# Alim_Ticketing_Slave.net
KiCad netlist of a schematic drawn in Altium Designer
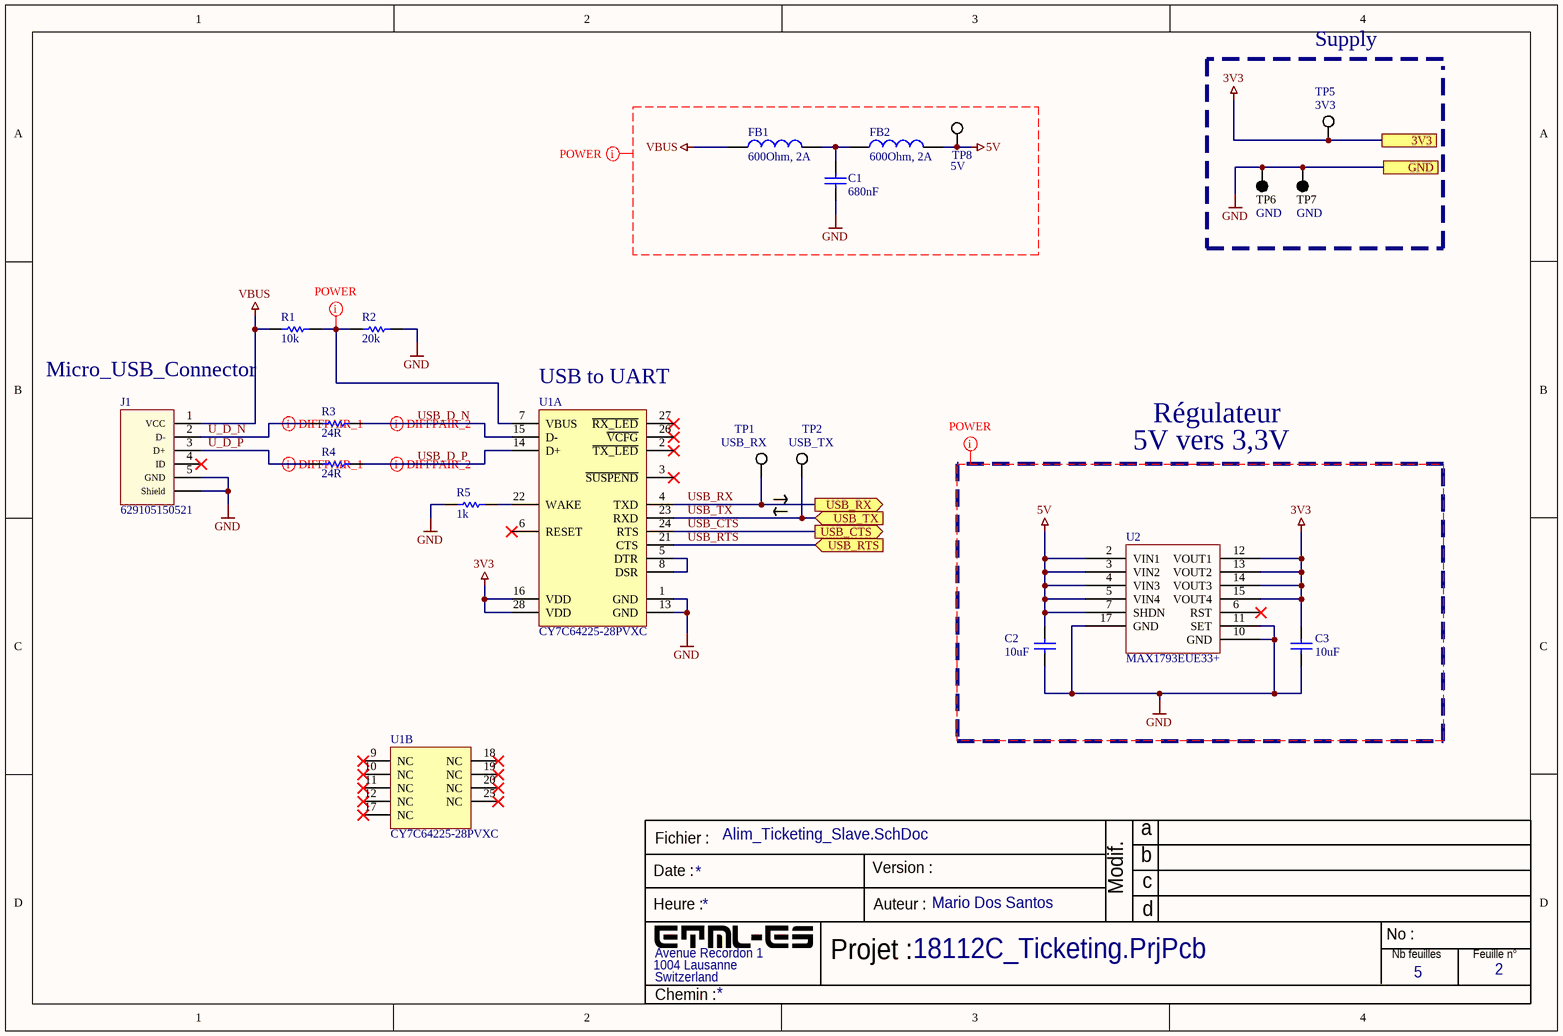
[diagram p0: Alim_Ticketing_Slave.SchDoc]

(export (version "E")
  (design (tool "Eeschema 10.0.6"))
  (components
    (comp (ref "C1")
      (value "680nF")
      (footprint "6-0805_N")
      (description "WCAP-CSGP General Purpose Ceramic Capacitors, size 0805, 100nF, +/-10%, 50VDC")
      (libsource (lib "VPA_v2b") (part "885012207098"))
    )
    (comp (ref "C2")
      (value "10uF")
      (footprint "6-0805_N")
      (description "Capacitor")
      (fields (field (name "PUBLISHER") "Altium Limited"))
      (libsource (lib "Miscellaneous Devices") (part "Cap"))
    )
    (comp (ref "C3")
      (value "10uF")
      (footprint "6-0805_N")
      (description "Capacitor")
      (fields (field (name "PUBLISHER") "Altium Limited"))
      (libsource (lib "Miscellaneous Devices") (part "Cap"))
    )
    (comp (ref "FB1")
      (value "600Ohm, 2A")
      (footprint "WE-CBF_0805_High Current")
      (description "WE-CBF SMT EMI Suppression Ferrite Bead, size 0805, 600Ohm, 2A")
      (fields (field (name "PART NUMBER") "742792040") (field (name "PUBLISHER") "Wurth Elektronik"))
      (libsource (lib "VPA_v2b") (part "742792040"))
    )
    (comp (ref "FB2")
      (value "600Ohm, 2A")
      (footprint "WE-CBF_0805_High Current")
      (description "WE-CBF SMT EMI Suppression Ferrite Bead, size 0805, 600Ohm, 2A")
      (fields (field (name "PART NUMBER") "742792040") (field (name "PUBLISHER") "Wurth Elektronik"))
      (libsource (lib "VPA_v2b") (part "742792040"))
    )
    (comp (ref "J1")
      (value "629105150521")
      (footprint "629105150521")
      (description "Micro USB 2.0 SMT Type B Horizontal 5 Contacts High Current WR-COM")
      (fields (field (name "PART NUMBER") "732-5960-1-ND") (field (name "PUBLISHER") "Wurth Elektronik"))
      (libsource (lib "PCB_Ticketing_Slave") (part "629105150521"))
    )
    (comp (ref "R1")
      (value "10k")
      (footprint "RESC0805(2012)_L")
      (description "100K 0.125W 5% 0805 (2012 Metric)  SMD")
      (fields (field (name "TOLERANCE") "5 %") (field (name "POWER") "0.125 W"))
      (libsource (lib "Altium Content Vault") (part "CMP-1013-00122-1"))
    )
    (comp (ref "R2")
      (value "20k")
      (footprint "RESC0805(2012)_L")
      (description "100K 0.125W 5% 0805 (2012 Metric)  SMD")
      (fields (field (name "TOLERANCE") "5 %") (field (name "POWER") "0.125 W"))
      (libsource (lib "Altium Content Vault") (part "CMP-1013-00122-1"))
    )
    (comp (ref "R3")
      (value "24R")
      (footprint "RESC0805(2012)_L")
      (description "100K 0.125W 5% 0805 (2012 Metric)  SMD")
      (fields (field (name "TOLERANCE") "5 %") (field (name "POWER") "0.125 W"))
      (libsource (lib "Altium Content Vault") (part "CMP-1013-00122-1"))
    )
    (comp (ref "R4")
      (value "24R")
      (footprint "RESC0805(2012)_L")
      (description "100K 0.125W 5% 0805 (2012 Metric)  SMD")
      (fields (field (name "TOLERANCE") "5 %") (field (name "POWER") "0.125 W"))
      (libsource (lib "Altium Content Vault") (part "CMP-1013-00122-1"))
    )
    (comp (ref "R5")
      (value "1k")
      (footprint "RESC0805(2012)_L")
      (description "100K 0.125W 5% 0805 (2012 Metric)  SMD")
      (fields (field (name "TOLERANCE") "5 %") (field (name "POWER") "0.125 W"))
      (libsource (lib "Altium Content Vault") (part "CMP-1013-00122-1"))
    )
    (comp (ref "TP1")
      (value "~")
      (footprint "KSTN-5019_V")
      (description "Test Point, 1 Position SMD, RoHS, Tape and Reel")
      (libsource (lib "Altium Content Vault") (part "TESTPOINT_WHITE"))
    )
    (comp (ref "TP2")
      (value "~")
      (footprint "KSTN-5019_V")
      (description "Test Point, 1 Position SMD, RoHS, Tape and Reel")
      (libsource (lib "Altium Content Vault") (part "TESTPOINT_WHITE"))
    )
    (comp (ref "TP5")
      (value "~")
      (footprint "KSTN-5019_V")
      (description "Test Point, 1 Position SMD, RoHS, Tape and Reel")
      (libsource (lib "Altium Content Vault") (part "TESTPOINT_WHITE"))
    )
    (comp (ref "TP6")
      (value "~")
      (footprint "KSTN-5011_V")
      (description "Test Point, Black, Through Hole, RoHS, Bulk,5011")
      (fields (field (name "MANUFACTURER") "Keystone"))
      (libsource (lib "Altium Content Vault") (part "TESTPOINT_BLACK"))
    )
    (comp (ref "TP7")
      (value "~")
      (footprint "KSTN-5011_V")
      (description "Test Point, Black, Through Hole, RoHS, Bulk,5011")
      (fields (field (name "MANUFACTURER") "Keystone"))
      (libsource (lib "Altium Content Vault") (part "TESTPOINT_BLACK"))
    )
    (comp (ref "TP8")
      (value "~")
      (footprint "KSTN-5019_V")
      (description "Test Point, 1 Position SMD, RoHS, Tape and Reel")
      (libsource (lib "Altium Content Vault") (part "TESTPOINT_WHITE"))
    )
    (comp (ref "U1")
      (value "CY7C64225-28PVXC")
      (footprint "CYP-PVX28_N")
      (description "USB-to-UART Bridge Controller, 3 to 5.25 V, 0 to 70 degC, 28-Pin SSOP (PVX28), Tube")
      (fields (field (name "MANUFACTURER") "Cypress") (field (name "PART NUMBER") "428-3158-ND"))
      (libsource (lib "PCB_Ticketing_Slave") (part "CMP-0967-00143-1"))
    )
    (comp (ref "U2")
      (value "MAX1793EUE33+")
      (footprint "TSOP65P640X110_HS-17N")
      (libsource (lib "2018A_CarteIoEscapeRoom_CAD") (part "MAX1793"))
    )
  )
  (nets
    (net (code "1") (name "/USB_CTS") (class "Default")
      (node (ref "U1") (pin "24") (pinfunction "RTS_24") (pintype "passive"))
    )
    (net (code "2") (name "/USB_D_N") (class "Default")
      (node (ref "R3") (pin "2") (pinfunction "2_2") (pintype "passive"))
      (node (ref "U1") (pin "15") (pinfunction "D-_15") (pintype "passive"))
    )
    (net (code "3") (name "/USB_D_P") (class "Default")
      (node (ref "R4") (pin "2") (pinfunction "2_2") (pintype "passive"))
      (node (ref "U1") (pin "14") (pinfunction "D+_14") (pintype "passive"))
    )
    (net (code "4") (name "/USB_RTS") (class "Default")
      (node (ref "U1") (pin "21") (pinfunction "CTS_21") (pintype "passive"))
    )
    (net (code "5") (name "/USB_RX") (class "Default")
      (node (ref "TP1") (pin "1") (pinfunction "1_1") (pintype "passive"))
      (node (ref "U1") (pin "4") (pinfunction "TXD_4") (pintype "passive"))
    )
    (net (code "6") (name "/USB_TX") (class "Default")
      (node (ref "TP2") (pin "1") (pinfunction "1_1") (pintype "passive"))
      (node (ref "U1") (pin "23") (pinfunction "RXD_23") (pintype "passive"))
    )
    (net (code "7") (name "/U_D_N") (class "Default")
      (node (ref "J1") (pin "2") (pinfunction "D-_2") (pintype "passive"))
      (node (ref "R3") (pin "1") (pinfunction "1_1") (pintype "passive"))
    )
    (net (code "8") (name "/U_D_P") (class "Default")
      (node (ref "J1") (pin "3") (pinfunction "D+_3") (pintype "passive"))
      (node (ref "R4") (pin "1") (pinfunction "1_1") (pintype "passive"))
    )
    (net (code "9") (name "3V3") (class "Default")
      (node (ref "C3") (pin "2") (pinfunction "2_2") (pintype "passive"))
      (node (ref "TP5") (pin "1") (pinfunction "1_1") (pintype "passive"))
      (node (ref "U1") (pin "16") (pinfunction "VDD_16") (pintype "passive"))
      (node (ref "U1") (pin "28") (pinfunction "VDD_28") (pintype "passive"))
      (node (ref "U2") (pin "12") (pinfunction "VOUT1_12") (pintype "passive"))
      (node (ref "U2") (pin "13") (pinfunction "VOUT2_13") (pintype "passive"))
      (node (ref "U2") (pin "14") (pinfunction "VOUT3_14") (pintype "passive"))
      (node (ref "U2") (pin "15") (pinfunction "VOUT4_15") (pintype "passive"))
    )
    (net (code "10") (name "5V") (class "Default")
      (node (ref "C2") (pin "1") (pinfunction "1_1") (pintype "passive"))
      (node (ref "FB2") (pin "2") (pinfunction "2_2") (pintype "passive"))
      (node (ref "TP8") (pin "1") (pinfunction "1_1") (pintype "passive"))
      (node (ref "U2") (pin "2") (pinfunction "VIN1_2") (pintype "passive"))
      (node (ref "U2") (pin "3") (pinfunction "VIN2_3") (pintype "passive"))
      (node (ref "U2") (pin "4") (pinfunction "VIN3_4") (pintype "passive"))
      (node (ref "U2") (pin "5") (pinfunction "VIN4_5") (pintype "passive"))
      (node (ref "U2") (pin "7") (pinfunction "SHDN_7") (pintype "passive"))
    )
    (net (code "11") (name "GND") (class "Default")
      (node (ref "C1") (pin "2") (pinfunction "2_2") (pintype "passive"))
      (node (ref "C2") (pin "2") (pinfunction "2_2") (pintype "passive"))
      (node (ref "C3") (pin "1") (pinfunction "1_1") (pintype "passive"))
      (node (ref "J1") (pin "5") (pinfunction "GND_5") (pintype "passive"))
      (node (ref "J1") (pin "Shell") (pinfunction "Shield_Shell") (pintype "passive"))
      (node (ref "R2") (pin "2") (pinfunction "2_2") (pintype "passive"))
      (node (ref "R5") (pin "2") (pinfunction "2_2") (pintype "passive"))
      (node (ref "TP6") (pin "1") (pinfunction "1_1") (pintype "passive"))
      (node (ref "TP7") (pin "1") (pinfunction "1_1") (pintype "passive"))
      (node (ref "U1") (pin "1") (pinfunction "GND_1") (pintype "passive"))
      (node (ref "U1") (pin "13") (pinfunction "GND_13") (pintype "passive"))
      (node (ref "U2") (pin "10") (pinfunction "GND_10") (pintype "power_in"))
      (node (ref "U2") (pin "11") (pinfunction "SET_11") (pintype "passive"))
      (node (ref "U2") (pin "17") (pinfunction "GND_17") (pintype "power_in"))
    )
    (net (code "12") (name "Net-(C1-Pad1)") (class "Default")
      (node (ref "C1") (pin "1") (pinfunction "1_1") (pintype "passive"))
      (node (ref "FB1") (pin "2") (pinfunction "2_2") (pintype "passive"))
      (node (ref "FB2") (pin "1") (pinfunction "1_1") (pintype "passive"))
    )
    (net (code "13") (name "Net-(U1A-DSR)") (class "Default")
      (node (ref "U1") (pin "5") (pinfunction "DTR_5") (pintype "passive"))
      (node (ref "U1") (pin "8") (pinfunction "DSR_8") (pintype "passive"))
    )
    (net (code "14") (name "Net-(U1A-VBUS)") (class "Default")
      (node (ref "R1") (pin "2") (pinfunction "2_2") (pintype "passive"))
      (node (ref "R2") (pin "1") (pinfunction "1_1") (pintype "passive"))
      (node (ref "U1") (pin "7") (pinfunction "VBUS_7") (pintype "passive"))
    )
    (net (code "15") (name "Net-(U1A-WAKE)") (class "Default")
      (node (ref "R5") (pin "1") (pinfunction "1_1") (pintype "passive"))
      (node (ref "U1") (pin "22") (pinfunction "WAKE_22") (pintype "passive"))
    )
    (net (code "16") (name "VBUS") (class "Default")
      (node (ref "FB1") (pin "1") (pinfunction "1_1") (pintype "passive"))
      (node (ref "J1") (pin "1") (pinfunction "VCC_1") (pintype "passive"))
      (node (ref "R1") (pin "1") (pinfunction "1_1") (pintype "passive"))
    )
    (net (code "17") (name "unconnected-(J1-ID-Pad4)") (class "Default")
      (node (ref "J1") (pin "4") (pinfunction "ID_4") (pintype "passive+no_connect"))
    )
    (net (code "18") (name "unconnected-(U1A-RESET-Pad6)") (class "Default")
      (node (ref "U1") (pin "6") (pinfunction "RESET_6") (pintype "passive+no_connect"))
    )
    (net (code "19") (name "unconnected-(U1A-~{RX_LED}-Pad27)") (class "Default")
      (node (ref "U1") (pin "27") (pinfunction "~{RX_LED}_27") (pintype "passive+no_connect"))
    )
    (net (code "20") (name "unconnected-(U1A-~{SUSPEND}-Pad3)") (class "Default")
      (node (ref "U1") (pin "3") (pinfunction "~{SUSPEND}_3") (pintype "passive+no_connect"))
    )
    (net (code "21") (name "unconnected-(U1A-~{TX_LED}-Pad2)") (class "Default")
      (node (ref "U1") (pin "2") (pinfunction "~{TX_LED}_2") (pintype "passive+no_connect"))
    )
    (net (code "22") (name "unconnected-(U1A-~{VCFG}-Pad26)") (class "Default")
      (node (ref "U1") (pin "26") (pinfunction "~{VCFG}_26") (pintype "passive+no_connect"))
    )
    (net (code "23") (name "unconnected-(U1B-NC-Pad9)") (class "Default")
      (node (ref "U1") (pin "9") (pinfunction "NC_9") (pintype "passive+no_connect"))
    )
    (net (code "24") (name "unconnected-(U1B-NC-Pad10)") (class "Default")
      (node (ref "U1") (pin "10") (pinfunction "NC_10") (pintype "passive+no_connect"))
    )
    (net (code "25") (name "unconnected-(U1B-NC-Pad11)") (class "Default")
      (node (ref "U1") (pin "11") (pinfunction "NC_11") (pintype "passive+no_connect"))
    )
    (net (code "26") (name "unconnected-(U1B-NC-Pad12)") (class "Default")
      (node (ref "U1") (pin "12") (pinfunction "NC_12") (pintype "passive+no_connect"))
    )
    (net (code "27") (name "unconnected-(U1B-NC-Pad17)") (class "Default")
      (node (ref "U1") (pin "17") (pinfunction "NC_17") (pintype "passive+no_connect"))
    )
    (net (code "28") (name "unconnected-(U1B-NC-Pad18)") (class "Default")
      (node (ref "U1") (pin "18") (pinfunction "NC_18") (pintype "passive+no_connect"))
    )
    (net (code "29") (name "unconnected-(U1B-NC-Pad19)") (class "Default")
      (node (ref "U1") (pin "19") (pinfunction "NC_19") (pintype "passive+no_connect"))
    )
    (net (code "30") (name "unconnected-(U1B-NC-Pad20)") (class "Default")
      (node (ref "U1") (pin "20") (pinfunction "NC_20") (pintype "passive+no_connect"))
    )
    (net (code "31") (name "unconnected-(U1B-NC-Pad25)") (class "Default")
      (node (ref "U1") (pin "25") (pinfunction "NC_25") (pintype "passive+no_connect"))
    )
    (net (code "32") (name "unconnected-(U2-RST-Pad6)") (class "Default")
      (node (ref "U2") (pin "6") (pinfunction "RST_6") (pintype "passive+no_connect"))
    )
  )
)
